# 04_16_2016.net
KiCad netlist of a schematic drawn in EAGLE
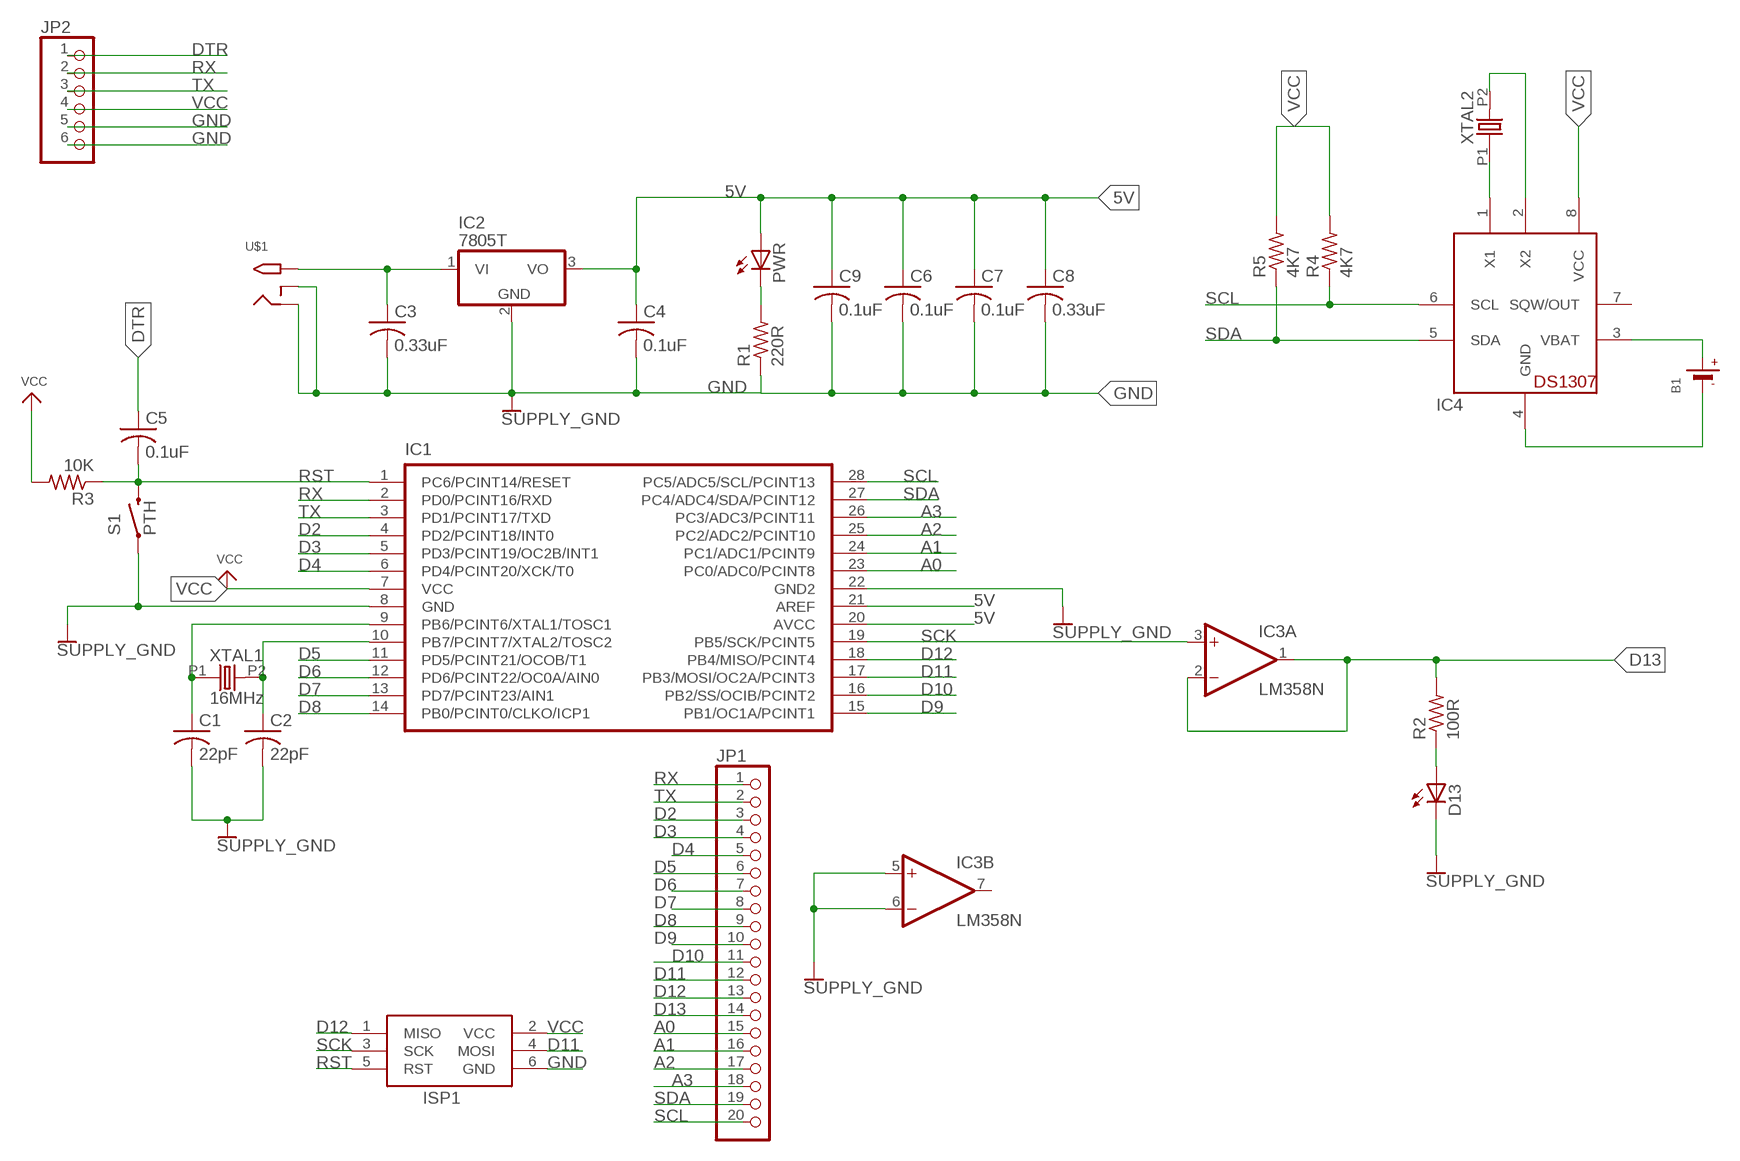
[diagram p0: schematic, sheet 1]

(export (version "E")
  (design (tool "Eeschema 10.0.6"))
  (components
    (comp (ref "B1")
      (value "BATTERYCR2032")
      (footprint "eagle-import:CR2032")
      (libsource (lib "eagle-import") (part "BATTERYCR2032"))
    )
    (comp (ref "C1")
      (value "22pF")
      (footprint "eagle-import:C050-025X075")
      (libsource (lib "eagle-import") (part "C-US050-025X075"))
    )
    (comp (ref "C2")
      (value "22pF")
      (footprint "eagle-import:C050-025X075")
      (libsource (lib "eagle-import") (part "C-US050-025X075"))
    )
    (comp (ref "C3")
      (value "0.33uF")
      (footprint "eagle-import:C050-025X075")
      (libsource (lib "eagle-import") (part "C-US050-025X075"))
    )
    (comp (ref "C4")
      (value "0.1uF")
      (footprint "eagle-import:C050-025X075")
      (libsource (lib "eagle-import") (part "C-US050-025X075"))
    )
    (comp (ref "C5")
      (value "0.1uF")
      (footprint "eagle-import:C050-025X075")
      (libsource (lib "eagle-import") (part "C-US050-025X075"))
    )
    (comp (ref "C6")
      (value "0.1uF")
      (footprint "eagle-import:C050-025X075")
      (libsource (lib "eagle-import") (part "C-US050-025X075"))
    )
    (comp (ref "C7")
      (value "0.1uF")
      (footprint "eagle-import:C050-025X075")
      (libsource (lib "eagle-import") (part "C-US050-025X075"))
    )
    (comp (ref "C8")
      (value "0.33uF")
      (footprint "eagle-import:C050-025X075")
      (libsource (lib "eagle-import") (part "C-US050-025X075"))
    )
    (comp (ref "C9")
      (value "0.1uF")
      (footprint "eagle-import:C050-025X075")
      (libsource (lib "eagle-import") (part "C-US050-025X075"))
    )
    (comp (ref "D13")
      (value "LED5MM")
      (footprint "eagle-import:LED5MM")
      (libsource (lib "eagle-import") (part "LED5MM"))
    )
    (comp (ref "IC1")
      (value "IC_UC_ATMEGA328PDIL")
      (footprint "eagle-import:DIL28-N")
      (libsource (lib "eagle-import") (part "IC_UC_ATMEGA328PDIL"))
    )
    (comp (ref "IC2")
      (value "7805T")
      (footprint "eagle-import:TO220H")
      (libsource (lib "eagle-import") (part "78T05"))
    )
    (comp (ref "IC3")
      (value "LM358N")
      (footprint "eagle-import:DIL08")
      (libsource (lib "eagle-import") (part "LM358N"))
    )
    (comp (ref "IC4")
      (value "DS1307")
      (footprint "eagle-import:DIL08")
      (libsource (lib "eagle-import") (part "DS1307"))
    )
    (comp (ref "ISP1")
      (value "AVRISP-6")
      (footprint "eagle-import:AVRISP")
      (libsource (lib "eagle-import") (part "AVRISP-6"))
    )
    (comp (ref "JP1")
      (value "PINHD-1X20-BIG")
      (footprint "eagle-import:1X20-BIG")
      (libsource (lib "eagle-import") (part "PINHD-1X20-BIG"))
    )
    (comp (ref "JP2")
      (value "PINHD-1X6")
      (footprint "eagle-import:1X06")
      (libsource (lib "eagle-import") (part "PINHD-1X6"))
    )
    (comp (ref "PWR")
      (value "LED5MM")
      (footprint "eagle-import:LED5MM")
      (libsource (lib "eagle-import") (part "LED5MM"))
    )
    (comp (ref "R1")
      (value "220R")
      (footprint "eagle-import:0207_10")
      (libsource (lib "eagle-import") (part "R-US_0207/10"))
    )
    (comp (ref "R2")
      (value "100R")
      (footprint "eagle-import:0207_10")
      (libsource (lib "eagle-import") (part "R-US_0207/10"))
    )
    (comp (ref "R3")
      (value "10K")
      (footprint "eagle-import:0207_10")
      (libsource (lib "eagle-import") (part "R-US_0207/10"))
    )
    (comp (ref "R4")
      (value "4K7")
      (footprint "eagle-import:0207_10")
      (libsource (lib "eagle-import") (part "R-US_0207/10"))
    )
    (comp (ref "R5")
      (value "4K7")
      (footprint "eagle-import:0207_10")
      (libsource (lib "eagle-import") (part "R-US_0207/10"))
    )
    (comp (ref "S1")
      (value "PTH")
      (footprint "eagle-import:TACTILE-PTH")
      (libsource (lib "eagle-import") (part "SWITCH-MOMENTARY-2PTH"))
    )
    (comp (ref "U$1")
      (value "2.1MMJACKTHM")
      (footprint "eagle-import:PJ-102A")
      (libsource (lib "eagle-import") (part "2.1MMJACKTHM"))
    )
    (comp (ref "XTAL1")
      (value "16MHz")
      (footprint "eagle-import:HC-49U-PTH")
      (libsource (lib "eagle-import") (part "OSC-XTAL-HC-49U-PTH"))
    )
    (comp (ref "XTAL2")
      (value "OSC-XTALTC-26")
      (footprint "eagle-import:TC-26")
      (libsource (lib "eagle-import") (part "OSC-XTALTC-26"))
    )
  )
  (nets
    (net (code "1") (name "/A0") (class "Default")
      (node (ref "IC1") (pin "23") (pinfunction "PC0/ADC0/PCINT8_23") (pintype "bidirectional"))
      (node (ref "JP1") (pin "15") (pinfunction "15_15") (pintype "passive"))
    )
    (net (code "2") (name "/A1") (class "Default")
      (node (ref "IC1") (pin "24") (pinfunction "PC1/ADC1/PCINT9_24") (pintype "bidirectional"))
      (node (ref "JP1") (pin "16") (pinfunction "16_16") (pintype "passive"))
    )
    (net (code "3") (name "/A2") (class "Default")
      (node (ref "IC1") (pin "25") (pinfunction "PC2/ADC2/PCINT10_25") (pintype "bidirectional"))
      (node (ref "JP1") (pin "17") (pinfunction "17_17") (pintype "passive"))
    )
    (net (code "4") (name "/A3") (class "Default")
      (node (ref "IC1") (pin "26") (pinfunction "PC3/ADC3/PCINT11_26") (pintype "bidirectional"))
      (node (ref "JP1") (pin "18") (pinfunction "18_18") (pintype "passive"))
    )
    (net (code "5") (name "/D2") (class "Default")
      (node (ref "IC1") (pin "4") (pinfunction "PD2/PCINT18/INT0_4") (pintype "bidirectional"))
      (node (ref "JP1") (pin "3") (pinfunction "3_3") (pintype "passive"))
    )
    (net (code "6") (name "/D3") (class "Default")
      (node (ref "IC1") (pin "5") (pinfunction "PD3/PCINT19/OC2B/INT1_5") (pintype "bidirectional"))
      (node (ref "JP1") (pin "4") (pinfunction "4_4") (pintype "passive"))
    )
    (net (code "7") (name "/D4") (class "Default")
      (node (ref "IC1") (pin "6") (pinfunction "PD4/PCINT20/XCK/T0_6") (pintype "bidirectional"))
      (node (ref "JP1") (pin "5") (pinfunction "5_5") (pintype "passive"))
    )
    (net (code "8") (name "/D5") (class "Default")
      (node (ref "IC1") (pin "11") (pinfunction "PD5/PCINT21/OCOB/T1_11") (pintype "bidirectional"))
      (node (ref "JP1") (pin "6") (pinfunction "6_6") (pintype "passive"))
    )
    (net (code "9") (name "/D6") (class "Default")
      (node (ref "IC1") (pin "12") (pinfunction "PD6/PCINT22/OC0A/AIN0_12") (pintype "bidirectional"))
      (node (ref "JP1") (pin "7") (pinfunction "7_7") (pintype "passive"))
    )
    (net (code "10") (name "/D7") (class "Default")
      (node (ref "IC1") (pin "13") (pinfunction "PD7/PCINT23/AIN1_13") (pintype "bidirectional"))
      (node (ref "JP1") (pin "8") (pinfunction "8_8") (pintype "passive"))
    )
    (net (code "11") (name "/D8") (class "Default")
      (node (ref "IC1") (pin "14") (pinfunction "PB0/PCINT0/CLKO/ICP1_14") (pintype "bidirectional"))
      (node (ref "JP1") (pin "9") (pinfunction "9_9") (pintype "passive"))
    )
    (net (code "12") (name "/D9") (class "Default")
      (node (ref "IC1") (pin "15") (pinfunction "PB1/OC1A/PCINT1_15") (pintype "bidirectional"))
      (node (ref "JP1") (pin "10") (pinfunction "10_10") (pintype "passive"))
    )
    (net (code "13") (name "/D10") (class "Default")
      (node (ref "IC1") (pin "16") (pinfunction "PB2/SS/OCIB/PCINT2_16") (pintype "bidirectional"))
      (node (ref "JP1") (pin "11") (pinfunction "11_11") (pintype "passive"))
    )
    (net (code "14") (name "/D11") (class "Default")
      (node (ref "IC1") (pin "17") (pinfunction "PB3/MOSI/OC2A/PCINT3_17") (pintype "bidirectional"))
      (node (ref "ISP1") (pin "4") (pinfunction "MOSI_4") (pintype "output"))
      (node (ref "JP1") (pin "12") (pinfunction "12_12") (pintype "passive"))
    )
    (net (code "15") (name "/D12") (class "Default")
      (node (ref "IC1") (pin "18") (pinfunction "PB4/MISO/PCINT4_18") (pintype "bidirectional"))
      (node (ref "ISP1") (pin "1") (pinfunction "MISO_1") (pintype "input"))
      (node (ref "JP1") (pin "13") (pinfunction "13_13") (pintype "passive"))
    )
    (net (code "16") (name "/RST") (class "Default")
      (node (ref "C5") (pin "2") (pinfunction "2_2") (pintype "passive"))
      (node (ref "IC1") (pin "1") (pinfunction "PC6/PCINT14/RESET_1") (pintype "bidirectional"))
      (node (ref "ISP1") (pin "5") (pinfunction "RST_5") (pintype "output"))
      (node (ref "R3") (pin "1") (pinfunction "1_1") (pintype "passive"))
      (node (ref "S1") (pin "3") (pinfunction "2_3") (pintype "passive"))
    )
    (net (code "17") (name "/RX") (class "Default")
      (node (ref "IC1") (pin "2") (pinfunction "PD0/PCINT16/RXD_2") (pintype "bidirectional"))
      (node (ref "JP1") (pin "1") (pinfunction "1_1") (pintype "passive"))
      (node (ref "JP2") (pin "2") (pinfunction "2_2") (pintype "passive"))
    )
    (net (code "18") (name "/SCK") (class "Default")
      (node (ref "IC1") (pin "19") (pinfunction "PB5/SCK/PCINT5_19") (pintype "bidirectional"))
      (node (ref "IC3") (pin "3") (pinfunction "+IN_3") (pintype "input"))
      (node (ref "ISP1") (pin "3") (pinfunction "SCK_3") (pintype "output"))
    )
    (net (code "19") (name "/SCL") (class "Default")
      (node (ref "IC1") (pin "28") (pinfunction "PC5/ADC5/SCL/PCINT13_28") (pintype "bidirectional"))
      (node (ref "IC4") (pin "6") (pinfunction "SCL_6") (pintype "bidirectional"))
      (node (ref "JP1") (pin "20") (pinfunction "20_20") (pintype "passive"))
      (node (ref "R4") (pin "1") (pinfunction "1_1") (pintype "passive"))
    )
    (net (code "20") (name "/SDA") (class "Default")
      (node (ref "IC1") (pin "27") (pinfunction "PC4/ADC4/SDA/PCINT12_27") (pintype "bidirectional"))
      (node (ref "IC4") (pin "5") (pinfunction "SDA_5") (pintype "bidirectional"))
      (node (ref "JP1") (pin "19") (pinfunction "19_19") (pintype "passive"))
      (node (ref "R5") (pin "1") (pinfunction "1_1") (pintype "passive"))
    )
    (net (code "21") (name "/TX") (class "Default")
      (node (ref "IC1") (pin "3") (pinfunction "PD1/PCINT17/TXD_3") (pintype "bidirectional"))
      (node (ref "JP1") (pin "2") (pinfunction "2_2") (pintype "passive"))
      (node (ref "JP2") (pin "3") (pinfunction "3_3") (pintype "passive"))
    )
    (net (code "22") (name "5V") (class "Default")
      (node (ref "C4") (pin "1") (pinfunction "1_1") (pintype "passive"))
      (node (ref "C6") (pin "1") (pinfunction "1_1") (pintype "passive"))
      (node (ref "C7") (pin "1") (pinfunction "1_1") (pintype "passive"))
      (node (ref "C8") (pin "1") (pinfunction "1_1") (pintype "passive"))
      (node (ref "C9") (pin "1") (pinfunction "1_1") (pintype "passive"))
      (node (ref "IC1") (pin "20") (pinfunction "AVCC_20") (pintype "bidirectional"))
      (node (ref "IC1") (pin "21") (pinfunction "AREF_21") (pintype "bidirectional"))
      (node (ref "IC2") (pin "3") (pinfunction "VO_3") (pintype "passive"))
      (node (ref "PWR") (pin "A") (pinfunction "A_A") (pintype "passive"))
    )
    (net (code "23") (name "D13") (class "Default")
      (node (ref "IC3") (pin "1") (pinfunction "OUT_1") (pintype "output"))
      (node (ref "IC3") (pin "2") (pinfunction "-IN_2") (pintype "input"))
      (node (ref "JP1") (pin "14") (pinfunction "14_14") (pintype "passive"))
      (node (ref "R2") (pin "2") (pinfunction "2_2") (pintype "passive"))
    )
    (net (code "24") (name "DTR") (class "Default")
      (node (ref "C5") (pin "1") (pinfunction "1_1") (pintype "passive"))
      (node (ref "JP2") (pin "1") (pinfunction "1_1") (pintype "passive"))
    )
    (net (code "25") (name "GND") (class "Default")
      (node (ref "C1") (pin "2") (pinfunction "2_2") (pintype "passive"))
      (node (ref "C2") (pin "2") (pinfunction "2_2") (pintype "passive"))
      (node (ref "C3") (pin "2") (pinfunction "2_2") (pintype "passive"))
      (node (ref "C4") (pin "2") (pinfunction "2_2") (pintype "passive"))
      (node (ref "C6") (pin "2") (pinfunction "2_2") (pintype "passive"))
      (node (ref "C7") (pin "2") (pinfunction "2_2") (pintype "passive"))
      (node (ref "C8") (pin "2") (pinfunction "2_2") (pintype "passive"))
      (node (ref "C9") (pin "2") (pinfunction "2_2") (pintype "passive"))
      (node (ref "D13") (pin "K") (pinfunction "C_K") (pintype "passive"))
      (node (ref "IC1") (pin "22") (pinfunction "GND2_22") (pintype "bidirectional"))
      (node (ref "IC1") (pin "8") (pinfunction "GND_8") (pintype "bidirectional"))
      (node (ref "IC2") (pin "2") (pinfunction "GND_2") (pintype "passive"))
      (node (ref "IC3") (pin "5") (pinfunction "+IN_5") (pintype "input"))
      (node (ref "IC3") (pin "6") (pinfunction "-IN_6") (pintype "input"))
      (node (ref "ISP1") (pin "6") (pinfunction "GND_6") (pintype "power_in"))
      (node (ref "JP2") (pin "5") (pinfunction "5_5") (pintype "passive"))
      (node (ref "JP2") (pin "6") (pinfunction "6_6") (pintype "passive"))
      (node (ref "R1") (pin "1") (pinfunction "1_1") (pintype "passive"))
      (node (ref "S1") (pin "1") (pinfunction "1_1") (pintype "passive"))
      (node (ref "U$1") (pin "RING") (pinfunction "RING_RING") (pintype "bidirectional"))
      (node (ref "U$1") (pin "RING_SW") (pinfunction "RING_SW_RING_SW") (pintype "bidirectional"))
    )
    (net (code "26") (name "Net-(D13-PadA)") (class "Default")
      (node (ref "D13") (pin "A") (pinfunction "A_A") (pintype "passive"))
      (node (ref "R2") (pin "1") (pinfunction "1_1") (pintype "passive"))
    )
    (net (code "27") (name "Net-(IC1-PB6{slash}PCINT6{slash}XTAL1{slash}TOSC1)") (class "Default")
      (node (ref "C1") (pin "1") (pinfunction "1_1") (pintype "passive"))
      (node (ref "IC1") (pin "9") (pinfunction "PB6/PCINT6/XTAL1/TOSC1_9") (pintype "bidirectional"))
      (node (ref "XTAL1") (pin "P1") (pinfunction "1_P1") (pintype "passive"))
    )
    (net (code "28") (name "Net-(IC1-PB7{slash}PCINT7{slash}XTAL2{slash}TOSC2)") (class "Default")
      (node (ref "C2") (pin "1") (pinfunction "1_1") (pintype "passive"))
      (node (ref "IC1") (pin "10") (pinfunction "PB7/PCINT7/XTAL2/TOSC2_10") (pintype "bidirectional"))
      (node (ref "XTAL1") (pin "P2") (pinfunction "2_P2") (pintype "passive"))
    )
    (net (code "29") (name "Net-(IC2-VI)") (class "Default")
      (node (ref "C3") (pin "1") (pinfunction "1_1") (pintype "passive"))
      (node (ref "IC2") (pin "1") (pinfunction "VI_1") (pintype "input"))
      (node (ref "U$1") (pin "TIP") (pinfunction "TIP_TIP") (pintype "bidirectional"))
    )
    (net (code "30") (name "Net-(IC4-GND)") (class "Default")
      (node (ref "B1") (pin "-") (pinfunction "-_-") (pintype "passive"))
      (node (ref "IC4") (pin "4") (pinfunction "GND_4") (pintype "power_in"))
    )
    (net (code "31") (name "Net-(IC4-VBAT)") (class "Default")
      (node (ref "B1") (pin "+") (pinfunction "+_+") (pintype "passive"))
      (node (ref "IC4") (pin "3") (pinfunction "VBAT_3") (pintype "power_in"))
    )
    (net (code "32") (name "Net-(IC4-X1)") (class "Default")
      (node (ref "IC4") (pin "1") (pinfunction "X1_1") (pintype "passive"))
      (node (ref "XTAL2") (pin "P1") (pinfunction "1_P1") (pintype "passive"))
    )
    (net (code "33") (name "Net-(IC4-X2)") (class "Default")
      (node (ref "IC4") (pin "2") (pinfunction "X2_2") (pintype "passive"))
      (node (ref "XTAL2") (pin "P2") (pinfunction "2_P2") (pintype "passive"))
    )
    (net (code "34") (name "Net-(PWR-C)") (class "Default")
      (node (ref "PWR") (pin "K") (pinfunction "C_K") (pintype "passive"))
      (node (ref "R1") (pin "2") (pinfunction "2_2") (pintype "passive"))
    )
    (net (code "35") (name "VCC") (class "Default")
      (node (ref "IC1") (pin "7") (pinfunction "VCC_7") (pintype "bidirectional"))
      (node (ref "IC4") (pin "8") (pinfunction "VCC_8") (pintype "power_in"))
      (node (ref "ISP1") (pin "2") (pinfunction "VCC_2") (pintype "power_in"))
      (node (ref "JP2") (pin "4") (pinfunction "4_4") (pintype "passive"))
      (node (ref "R3") (pin "2") (pinfunction "2_2") (pintype "passive"))
      (node (ref "R4") (pin "2") (pinfunction "2_2") (pintype "passive"))
      (node (ref "R5") (pin "2") (pinfunction "2_2") (pintype "passive"))
    )
    (net (code "36") (name "unconnected-(IC3B-OUT-Pad7)") (class "Default")
      (node (ref "IC3") (pin "7") (pinfunction "OUT_7") (pintype "output"))
    )
    (net (code "37") (name "unconnected-(IC4-SQW{slash}OUT-Pad7)") (class "Default")
      (node (ref "IC4") (pin "7") (pinfunction "SQW/OUT_7") (pintype "bidirectional"))
    )
  )
)
